# Condor2__Power_REV_C.net
KiCad netlist of a schematic drawn in Altium Designer
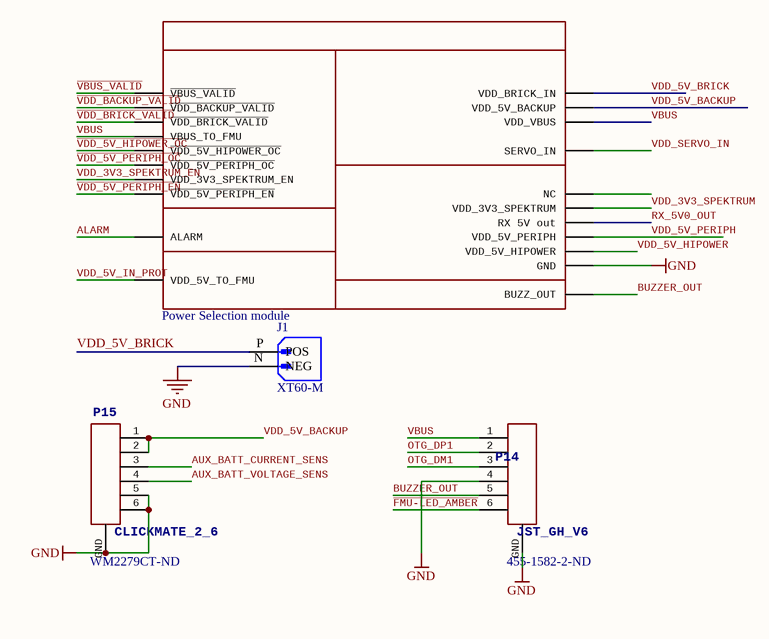
[diagram p0: Condor2__Power_REV_C.SchDoc]

(export (version "E")
  (design (tool "Eeschema 10.0.6"))
  (components
    (comp (ref "J1")
      (value "XT60-M")
      (footprint "AMASS_XT60-M")
      (description "Plug; DC supply; XT60; male; PIN: 2; for cable; soldered; 30A; 500V")
      (fields (field (name "MF") "AMASS"))
      (libsource (lib "CB_REV_C") (part "XT60-M"))
    )
    (comp (ref "P14")
      (value "JST_GH_V6")
      (footprint "JST_GH_V6")
      (description "BM06B-GHS-TBT")
      (fields (field (name "SUPPLIER PART NUMBER 1") "455-1582-2-ND"))
      (libsource (lib "CB_REV_C") (part "JST_GH_V6"))
    )
    (comp (ref "P15")
      (value "CLICKMATE_2_6")
      (footprint "CLICKMATE_V6_2MM")
      (description "Connector, Header, 6Pos, 2.54MM, Vert, THT, Au")
      (fields (field (name "SUPPLIER PART NUMBER 1") "WM2279CT-ND"))
      (libsource (lib "CB_REV_C") (part "CLICKMATE_2_6"))
    )
    (comp (ref "PSM1")
      (value "Power Selection module")
      (footprint "PSM")
      (description "PCA, PSM, Assembly")
      (libsource (lib "CB_REV_C") (part "PSMPSM"))
    )
  )
  (nets
    (net (code "1") (name "/ALARM") (class "Default")
      (node (ref "PSM1") (pin "ALARM") (pinfunction "ALARM_ALARM") (pintype "passive"))
    )
    (net (code "2") (name "/AUX_BATT_CURRENT_SENS") (class "Default")
      (node (ref "P15") (pin "3") (pinfunction "3_3") (pintype "passive"))
    )
    (net (code "3") (name "/AUX_BATT_VOLTAGE_SENS") (class "Default")
      (node (ref "P15") (pin "4") (pinfunction "4_4") (pintype "passive"))
    )
    (net (code "4") (name "/BUZZER_OUT") (class "Default")
      (node (ref "P14") (pin "5") (pinfunction "5_5") (pintype "passive"))
      (node (ref "PSM1") (pin "BUZZER_OUT") (pinfunction "BUZZ_OUT_BUZZER_OUT") (pintype "passive"))
    )
    (net (code "5") (name "/OTG_DM1") (class "Default")
      (node (ref "P14") (pin "3") (pinfunction "3_3") (pintype "passive"))
    )
    (net (code "6") (name "/OTG_DP1") (class "Default")
      (node (ref "P14") (pin "2") (pinfunction "2_2") (pintype "passive"))
    )
    (net (code "7") (name "/RX_5V0_OUT") (class "Default")
      (node (ref "PSM1") (pin "RX") (pinfunction "RX_5V_out_RX") (pintype "passive"))
    )
    (net (code "8") (name "/VBUS") (class "Default")
      (node (ref "P14") (pin "1") (pinfunction "1_1") (pintype "passive"))
      (node (ref "PSM1") (pin "VBUS") (pinfunction "VBUS_TO_FMU_VBUS") (pintype "passive"))
      (node (ref "PSM1") (pin "VDD_VBUS") (pinfunction "VDD_VBUS_VDD_VBUS") (pintype "passive"))
    )
    (net (code "9") (name "/VDD_3V3_SPEKTRUM") (class "Default")
      (node (ref "PSM1") (pin "SPEK") (pinfunction "VDD_3V3_SPEKTRUM_SPEK") (pintype "passive"))
    )
    (net (code "10") (name "/VDD_3V3_SPEKTRUM_EN") (class "Default")
      (node (ref "PSM1") (pin "VDD_3V3_SPEKTRUM_EN") (pinfunction "VDD_3V3_SPEKTRUM_EN_VDD_3V3_SPEKTRUM_EN") (pintype "passive"))
    )
    (net (code "11") (name "/VDD_5V_BACKUP") (class "Default")
      (node (ref "P15") (pin "1") (pinfunction "1_1") (pintype "passive"))
      (node (ref "P15") (pin "2") (pinfunction "2_2") (pintype "passive"))
      (node (ref "PSM1") (pin "VDD_5V_BACKUP") (pinfunction "VDD_5V_BACKUP_VDD_5V_BACKUP") (pintype "passive"))
    )
    (net (code "12") (name "/VDD_5V_BRICK") (class "Default")
      (node (ref "J1") (pin "P") (pinfunction "POS_P") (pintype "passive"))
      (node (ref "PSM1") (pin "VDD_BRICK_IN") (pinfunction "VDD_BRICK_IN_VDD_BRICK_IN") (pintype "passive"))
    )
    (net (code "13") (name "/VDD_5V_HIPOWER") (class "Default")
      (node (ref "PSM1") (pin "5V_HIPOWER") (pinfunction "VDD_5V_HIPOWER_5V_HIPOWER") (pintype "passive"))
    )
    (net (code "14") (name "/VDD_5V_IN_PROT") (class "Default")
      (node (ref "PSM1") (pin "VDD_5V_IN_PROT") (pinfunction "VDD_5V_TO_FMU_VDD_5V_IN_PROT") (pintype "passive"))
    )
    (net (code "15") (name "/VDD_5V_PERIPH") (class "Default")
      (node (ref "PSM1") (pin "5V_PERIPH") (pinfunction "VDD_5V_PERIPH_5V_PERIPH") (pintype "passive"))
    )
    (net (code "16") (name "/VDD_SERVO_IN") (class "Default")
      (node (ref "PSM1") (pin "SERVO_IN") (pinfunction "SERVO_IN_SERVO_IN") (pintype "passive"))
    )
    (net (code "17") (name "/~{FMU-LED_AMBER}") (class "Default")
      (node (ref "P14") (pin "6") (pinfunction "6_6") (pintype "passive"))
    )
    (net (code "18") (name "/~{VBUS_VALID}") (class "Default")
      (node (ref "PSM1") (pin "!VBUS_VALID") (pinfunction "~{VBUS_VALID}_!VBUS_VALID") (pintype "passive"))
    )
    (net (code "19") (name "/~{VDD_5V_HIPOWER_OC}") (class "Default")
      (node (ref "PSM1") (pin "!VDD_5V_HIPOWER_OC") (pinfunction "~{VDD_5V_HIPOWER_OC}_!VDD_5V_HIPOWER_OC") (pintype "passive"))
    )
    (net (code "20") (name "/~{VDD_5V_PERIPH_EN}") (class "Default")
      (node (ref "PSM1") (pin "!VDD_5V_PERIPH_EN") (pinfunction "~{VDD_5V_PERIPH_EN}_!VDD_5V_PERIPH_EN") (pintype "passive"))
    )
    (net (code "21") (name "/~{VDD_5V_PERIPH_OC}") (class "Default")
      (node (ref "PSM1") (pin "!VDD_5V_PERIPH_OC") (pinfunction "~{VDD_5V_PERIPH_OC}_!VDD_5V_PERIPH_OC") (pintype "passive"))
    )
    (net (code "22") (name "/~{VDD_BACKUP_VALID}") (class "Default")
      (node (ref "PSM1") (pin "!VDD_BACKUP_VALID") (pinfunction "~{VDD_BACKUP_VALID}_!VDD_BACKUP_VALID") (pintype "passive"))
    )
    (net (code "23") (name "/~{VDD_BRICK_VALID}") (class "Default")
      (node (ref "PSM1") (pin "!VDD_BRICK_VALID") (pinfunction "~{VDD_BRICK_VALID}_!VDD_BRICK_VALID") (pintype "passive"))
    )
    (net (code "24") (name "GND") (class "Default")
      (node (ref "J1") (pin "N") (pinfunction "NEG_N") (pintype "passive"))
      (node (ref "P14") (pin "4") (pinfunction "4_4") (pintype "passive"))
      (node (ref "P14") (pin "GND") (pinfunction "GND_GND") (pintype "passive"))
      (node (ref "P15") (pin "5") (pinfunction "5_5") (pintype "passive"))
      (node (ref "P15") (pin "6") (pinfunction "6_6") (pintype "passive"))
      (node (ref "P15") (pin "GND") (pinfunction "GND_GND") (pintype "passive"))
      (node (ref "PSM1") (pin "GND") (pinfunction "GND_GND") (pintype "passive"))
    )
    (net (code "25") (name "unconnected-(PSM1-PadNC)") (class "Default")
      (node (ref "PSM1") (pin "NC") (pinfunction "NC_NC") (pintype "passive"))
    )
  )
)
